# quadcopter.net
KiCad netlist of a schematic drawn in EAGLE
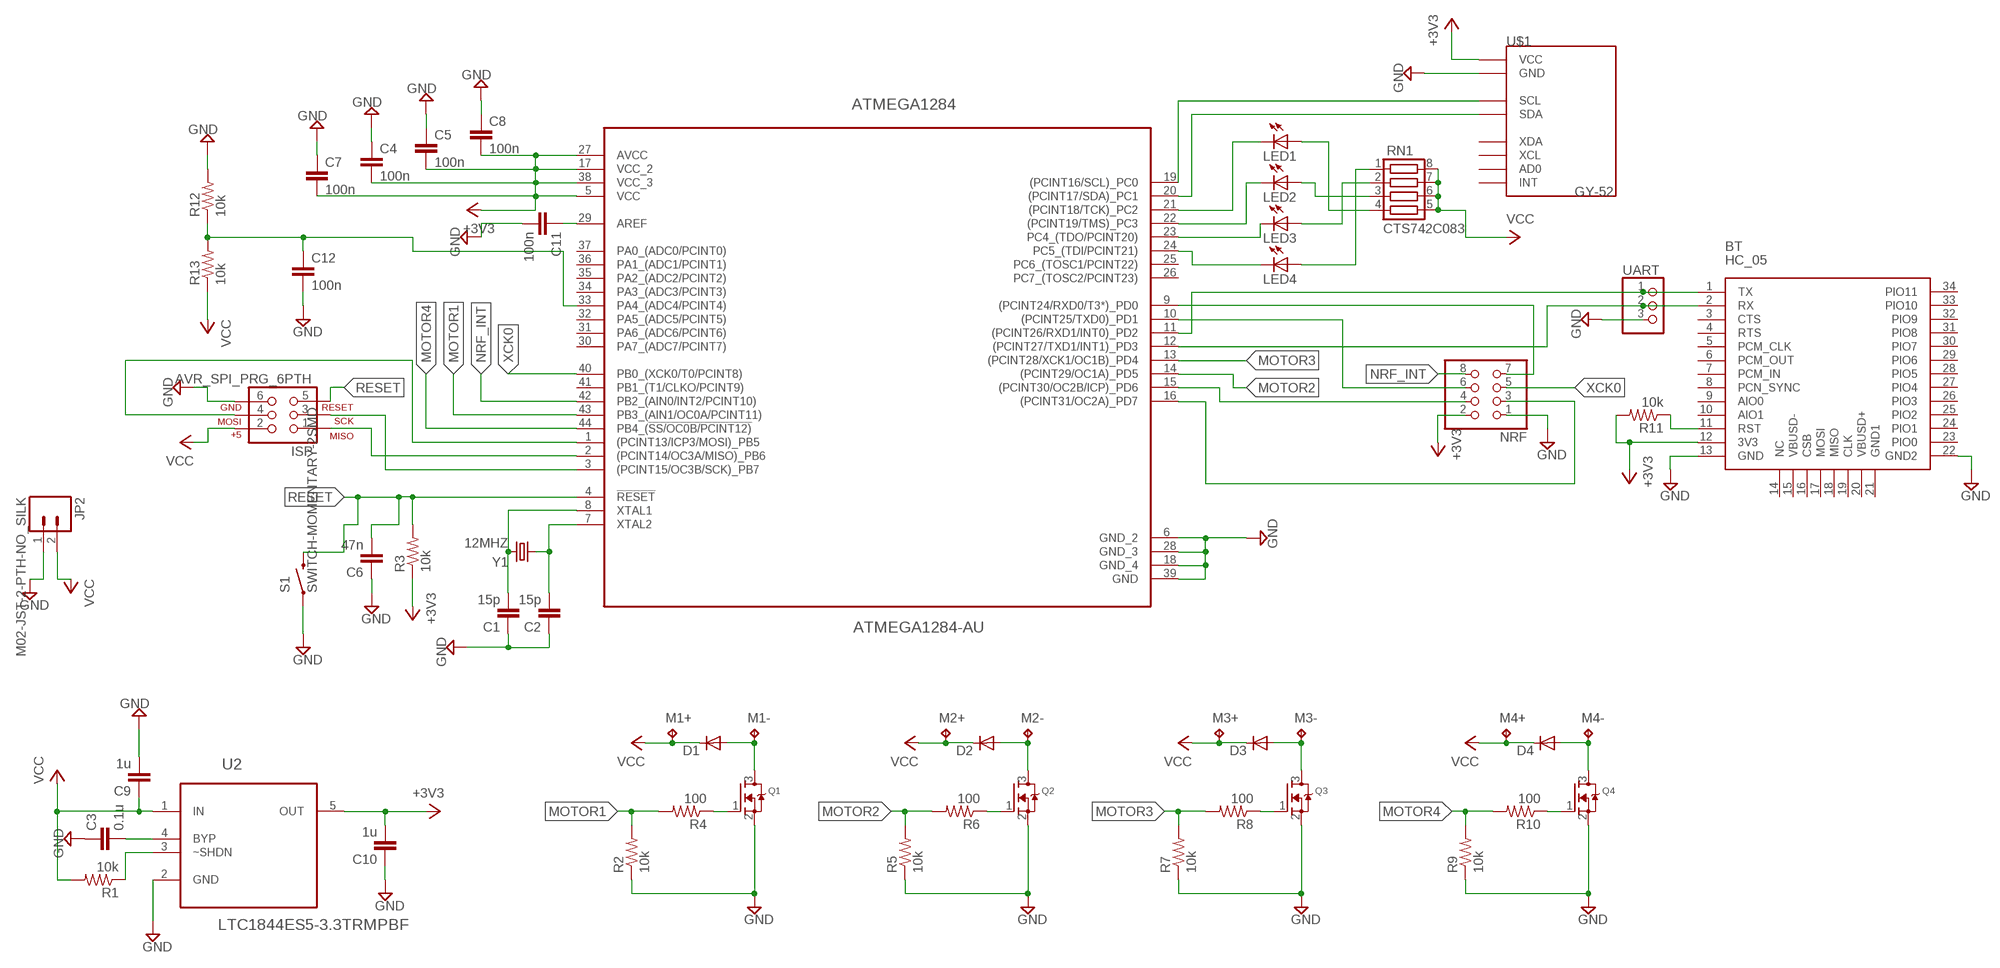
[diagram p0: schematic, sheet 1]

(export (version "E")
  (design (tool "Eeschema 10.0.6"))
  (components
    (comp (ref "ATMEGA1284")
      (value "ATMEGA1284-AU")
      (footprint "eagle-import:QFP80P1200X1200X120-44N")
      (libsource (lib "eagle-import") (part "ATMEGA1284-AU"))
    )
    (comp (ref "BT")
      (value "HC_05")
      (footprint "eagle-import:BLUETOOTH_SMD")
      (libsource (lib "eagle-import") (part "HC_05"))
    )
    (comp (ref "C1")
      (value "15p")
      (footprint "eagle-import:0603-CAP")
      (libsource (lib "eagle-import") (part "10UF-6.3V-20%(0603)"))
    )
    (comp (ref "C2")
      (value "15p")
      (footprint "eagle-import:0603-CAP")
      (libsource (lib "eagle-import") (part "10UF-6.3V-20%(0603)"))
    )
    (comp (ref "C3")
      (value "0.1u")
      (footprint "eagle-import:0603-CAP")
      (libsource (lib "eagle-import") (part "10UF-6.3V-20%(0603)"))
    )
    (comp (ref "C4")
      (value "100n")
      (footprint "eagle-import:0603-CAP")
      (libsource (lib "eagle-import") (part "10UF-6.3V-20%(0603)"))
    )
    (comp (ref "C5")
      (value "100n")
      (footprint "eagle-import:0603-CAP")
      (libsource (lib "eagle-import") (part "10UF-6.3V-20%(0603)"))
    )
    (comp (ref "C6")
      (value "47n")
      (footprint "eagle-import:0603-CAP")
      (libsource (lib "eagle-import") (part "10UF-6.3V-20%(0603)"))
    )
    (comp (ref "C7")
      (value "100n")
      (footprint "eagle-import:0603-CAP")
      (libsource (lib "eagle-import") (part "10UF-6.3V-20%(0603)"))
    )
    (comp (ref "C8")
      (value "100n")
      (footprint "eagle-import:0603-CAP")
      (libsource (lib "eagle-import") (part "10UF-6.3V-20%(0603)"))
    )
    (comp (ref "C9")
      (value "1u")
      (footprint "eagle-import:0603-CAP")
      (libsource (lib "eagle-import") (part "10UF-6.3V-20%(0603)"))
    )
    (comp (ref "C10")
      (value "1u")
      (footprint "eagle-import:0603-CAP")
      (libsource (lib "eagle-import") (part "10UF-6.3V-20%(0603)"))
    )
    (comp (ref "C11")
      (value "100n")
      (footprint "eagle-import:0603-CAP")
      (libsource (lib "eagle-import") (part "10UF-6.3V-20%(0603)"))
    )
    (comp (ref "C12")
      (value "100n")
      (footprint "eagle-import:0603-CAP")
      (libsource (lib "eagle-import") (part "10UF-6.3V-20%(0603)"))
    )
    (comp (ref "D1")
      (value "DIODE-SMB")
      (footprint "eagle-import:SMB")
      (libsource (lib "eagle-import") (part "DIODE-SMB"))
    )
    (comp (ref "D2")
      (value "DIODE-SMB")
      (footprint "eagle-import:SMB")
      (libsource (lib "eagle-import") (part "DIODE-SMB"))
    )
    (comp (ref "D3")
      (value "DIODE-SMB")
      (footprint "eagle-import:SMB")
      (libsource (lib "eagle-import") (part "DIODE-SMB"))
    )
    (comp (ref "D4")
      (value "DIODE-SMB")
      (footprint "eagle-import:SMB")
      (libsource (lib "eagle-import") (part "DIODE-SMB"))
    )
    (comp (ref "ISP")
      (value "AVR_SPI_PRG_6PTH")
      (footprint "eagle-import:2X3")
      (libsource (lib "eagle-import") (part "AVR_SPI_PRG_6PTH"))
    )
    (comp (ref "JP2")
      (value "M02-JST-2-PTH-NO_SILK")
      (footprint "eagle-import:JST-2-PTH-NS")
      (libsource (lib "eagle-import") (part "M02-JST-2-PTH-NO_SILK"))
    )
    (comp (ref "LED1")
      (value "LEDCHIP-LED0805")
      (footprint "eagle-import:CHIP-LED0805")
      (libsource (lib "eagle-import") (part "LEDCHIP-LED0805"))
    )
    (comp (ref "LED2")
      (value "LEDCHIP-LED0805")
      (footprint "eagle-import:CHIP-LED0805")
      (libsource (lib "eagle-import") (part "LEDCHIP-LED0805"))
    )
    (comp (ref "LED3")
      (value "LEDCHIP-LED0805")
      (footprint "eagle-import:CHIP-LED0805")
      (libsource (lib "eagle-import") (part "LEDCHIP-LED0805"))
    )
    (comp (ref "LED4")
      (value "LEDCHIP-LED0805")
      (footprint "eagle-import:CHIP-LED0805")
      (libsource (lib "eagle-import") (part "LEDCHIP-LED0805"))
    )
    (comp (ref "M1+")
      (value "TPTP20SQ")
      (footprint "eagle-import:TP20SQ")
      (libsource (lib "eagle-import") (part "TPTP20SQ"))
    )
    (comp (ref "M1-")
      (value "TPTP20SQ")
      (footprint "eagle-import:TP20SQ")
      (libsource (lib "eagle-import") (part "TPTP20SQ"))
    )
    (comp (ref "M2+")
      (value "TPTP20SQ")
      (footprint "eagle-import:TP20SQ")
      (libsource (lib "eagle-import") (part "TPTP20SQ"))
    )
    (comp (ref "M2-")
      (value "TPTP20SQ")
      (footprint "eagle-import:TP20SQ")
      (libsource (lib "eagle-import") (part "TPTP20SQ"))
    )
    (comp (ref "M3+")
      (value "TPTP20SQ")
      (footprint "eagle-import:TP20SQ")
      (libsource (lib "eagle-import") (part "TPTP20SQ"))
    )
    (comp (ref "M3-")
      (value "TPTP20SQ")
      (footprint "eagle-import:TP20SQ")
      (libsource (lib "eagle-import") (part "TPTP20SQ"))
    )
    (comp (ref "M4+")
      (value "TPTP20SQ")
      (footprint "eagle-import:TP20SQ")
      (libsource (lib "eagle-import") (part "TPTP20SQ"))
    )
    (comp (ref "M4-")
      (value "TPTP20SQ")
      (footprint "eagle-import:TP20SQ")
      (libsource (lib "eagle-import") (part "TPTP20SQ"))
    )
    (comp (ref "NRF")
      (value "PINHD-2X4")
      (footprint "eagle-import:2X04")
      (libsource (lib "eagle-import") (part "PINHD-2X4"))
    )
    (comp (ref "Q1")
      (value "MOSFET-NREFLOW")
      (footprint "eagle-import:SOT23")
      (libsource (lib "eagle-import") (part "MOSFET-NREFLOW"))
    )
    (comp (ref "Q2")
      (value "MOSFET-NREFLOW")
      (footprint "eagle-import:SOT23")
      (libsource (lib "eagle-import") (part "MOSFET-NREFLOW"))
    )
    (comp (ref "Q3")
      (value "MOSFET-NREFLOW")
      (footprint "eagle-import:SOT23")
      (libsource (lib "eagle-import") (part "MOSFET-NREFLOW"))
    )
    (comp (ref "Q4")
      (value "MOSFET-NREFLOW")
      (footprint "eagle-import:SOT23")
      (libsource (lib "eagle-import") (part "MOSFET-NREFLOW"))
    )
    (comp (ref "R1")
      (value "10k")
      (footprint "eagle-import:0603-RES")
      (libsource (lib "eagle-import") (part "2.0KOHM1/10W5%(0603)"))
    )
    (comp (ref "R2")
      (value "10k")
      (footprint "eagle-import:0603-RES")
      (libsource (lib "eagle-import") (part "2.0KOHM1/10W5%(0603)"))
    )
    (comp (ref "R3")
      (value "10k")
      (footprint "eagle-import:0603-RES")
      (libsource (lib "eagle-import") (part "2.0KOHM1/10W5%(0603)"))
    )
    (comp (ref "R4")
      (value "100")
      (footprint "eagle-import:0603-RES")
      (libsource (lib "eagle-import") (part "2.0KOHM1/10W5%(0603)"))
    )
    (comp (ref "R5")
      (value "10k")
      (footprint "eagle-import:0603-RES")
      (libsource (lib "eagle-import") (part "2.0KOHM1/10W5%(0603)"))
    )
    (comp (ref "R6")
      (value "100")
      (footprint "eagle-import:0603-RES")
      (libsource (lib "eagle-import") (part "2.0KOHM1/10W5%(0603)"))
    )
    (comp (ref "R7")
      (value "10k")
      (footprint "eagle-import:0603-RES")
      (libsource (lib "eagle-import") (part "2.0KOHM1/10W5%(0603)"))
    )
    (comp (ref "R8")
      (value "100")
      (footprint "eagle-import:0603-RES")
      (libsource (lib "eagle-import") (part "2.0KOHM1/10W5%(0603)"))
    )
    (comp (ref "R9")
      (value "10k")
      (footprint "eagle-import:0603-RES")
      (libsource (lib "eagle-import") (part "2.0KOHM1/10W5%(0603)"))
    )
    (comp (ref "R10")
      (value "100")
      (footprint "eagle-import:0603-RES")
      (libsource (lib "eagle-import") (part "2.0KOHM1/10W5%(0603)"))
    )
    (comp (ref "R11")
      (value "10k")
      (footprint "eagle-import:0603-RES")
      (libsource (lib "eagle-import") (part "2.0KOHM1/10W5%(0603)"))
    )
    (comp (ref "R12")
      (value "10k")
      (footprint "eagle-import:0603-RES")
      (libsource (lib "eagle-import") (part "2.0KOHM1/10W5%(0603)"))
    )
    (comp (ref "R13")
      (value "10k")
      (footprint "eagle-import:0603-RES")
      (libsource (lib "eagle-import") (part "2.0KOHM1/10W5%(0603)"))
    )
    (comp (ref "RN1")
      (value "CTS742C083")
      (footprint "eagle-import:CTS742C083")
      (libsource (lib "eagle-import") (part "CTS742C083"))
    )
    (comp (ref "S1")
      (value "SWITCH-MOMENTARY-2SMD")
      (footprint "eagle-import:TACTILE_SWITCH_SMD")
      (libsource (lib "eagle-import") (part "SWITCH-MOMENTARY-2SMD"))
    )
    (comp (ref "U$1")
      (value "GY-52")
      (footprint "eagle-import:PDIP-8")
      (libsource (lib "eagle-import") (part "GY-52"))
    )
    (comp (ref "U2")
      (value "LTC1844ES5-3.3TRMPBF")
      (footprint "eagle-import:SOT95P280X100-5N")
      (fields (field (name "MPN") "LTC1844ES5-3.3#TRMPBF"))
      (libsource (lib "eagle-import") (part "LTC1844ES5-3.3TRMPBF"))
    )
    (comp (ref "UART")
      (value "PINHD-1X3")
      (footprint "eagle-import:1X03")
      (libsource (lib "eagle-import") (part "PINHD-1X3"))
    )
    (comp (ref "Y1")
      (value "12MHZ")
      (footprint "eagle-import:TXC-SMD-CRYSTAL")
      (libsource (lib "eagle-import") (part "CRYSTAL"))
    )
  )
  (nets
    (net (code "1") (name "+3V3") (class "Default")
      (node (ref "ATMEGA1284") (pin "17") (pinfunction "VCC_2_17") (pintype "power_in"))
      (node (ref "ATMEGA1284") (pin "27") (pinfunction "AVCC_27") (pintype "power_in"))
      (node (ref "ATMEGA1284") (pin "38") (pinfunction "VCC_3_38") (pintype "power_in"))
      (node (ref "ATMEGA1284") (pin "5") (pinfunction "VCC_5") (pintype "power_in"))
      (node (ref "BT") (pin "12") (pinfunction "3V3_12") (pintype "bidirectional"))
      (node (ref "C10") (pin "2") (pinfunction "2_2") (pintype "passive"))
      (node (ref "C4") (pin "2") (pinfunction "2_2") (pintype "passive"))
      (node (ref "C5") (pin "2") (pinfunction "2_2") (pintype "passive"))
      (node (ref "C7") (pin "2") (pinfunction "2_2") (pintype "passive"))
      (node (ref "C8") (pin "2") (pinfunction "2_2") (pintype "passive"))
      (node (ref "NRF") (pin "2") (pinfunction "2_2") (pintype "passive"))
      (node (ref "R11") (pin "2") (pinfunction "2_2") (pintype "passive"))
      (node (ref "R3") (pin "1") (pinfunction "1_1") (pintype "passive"))
      (node (ref "U$1") (pin "P$2") (pinfunction "VCC_P$2") (pintype "bidirectional"))
      (node (ref "U2") (pin "5") (pinfunction "OUT_5") (pintype "output"))
    )
    (net (code "2") (name "GND") (class "Default")
      (node (ref "ATMEGA1284") (pin "18") (pinfunction "GND_4_18") (pintype "passive"))
      (node (ref "ATMEGA1284") (pin "28") (pinfunction "GND_3_28") (pintype "passive"))
      (node (ref "ATMEGA1284") (pin "39") (pinfunction "GND_39") (pintype "passive"))
      (node (ref "ATMEGA1284") (pin "6") (pinfunction "GND_2_6") (pintype "passive"))
      (node (ref "BT") (pin "13") (pinfunction "GND_13") (pintype "bidirectional"))
      (node (ref "BT") (pin "22") (pinfunction "GND2_22") (pintype "bidirectional"))
      (node (ref "C1") (pin "1") (pinfunction "1_1") (pintype "passive"))
      (node (ref "C10") (pin "1") (pinfunction "1_1") (pintype "passive"))
      (node (ref "C11") (pin "2") (pinfunction "2_2") (pintype "passive"))
      (node (ref "C12") (pin "2") (pinfunction "2_2") (pintype "passive"))
      (node (ref "C2") (pin "1") (pinfunction "1_1") (pintype "passive"))
      (node (ref "C3") (pin "1") (pinfunction "1_1") (pintype "passive"))
      (node (ref "C4") (pin "1") (pinfunction "1_1") (pintype "passive"))
      (node (ref "C5") (pin "1") (pinfunction "1_1") (pintype "passive"))
      (node (ref "C6") (pin "1") (pinfunction "1_1") (pintype "passive"))
      (node (ref "C7") (pin "1") (pinfunction "1_1") (pintype "passive"))
      (node (ref "C8") (pin "1") (pinfunction "1_1") (pintype "passive"))
      (node (ref "C9") (pin "2") (pinfunction "2_2") (pintype "passive"))
      (node (ref "ISP") (pin "6") (pinfunction "6_6") (pintype "passive"))
      (node (ref "JP2") (pin "1") (pinfunction "1_1") (pintype "passive"))
      (node (ref "NRF") (pin "1") (pinfunction "1_1") (pintype "passive"))
      (node (ref "Q1") (pin "2") (pinfunction "S_2") (pintype "bidirectional"))
      (node (ref "Q2") (pin "2") (pinfunction "S_2") (pintype "bidirectional"))
      (node (ref "Q3") (pin "2") (pinfunction "S_2") (pintype "bidirectional"))
      (node (ref "Q4") (pin "2") (pinfunction "S_2") (pintype "bidirectional"))
      (node (ref "R12") (pin "2") (pinfunction "2_2") (pintype "passive"))
      (node (ref "R2") (pin "1") (pinfunction "1_1") (pintype "passive"))
      (node (ref "R5") (pin "1") (pinfunction "1_1") (pintype "passive"))
      (node (ref "R7") (pin "1") (pinfunction "1_1") (pintype "passive"))
      (node (ref "R9") (pin "1") (pinfunction "1_1") (pintype "passive"))
      (node (ref "S1") (pin "1") (pinfunction "1_1") (pintype "passive"))
      (node (ref "U$1") (pin "P$8") (pinfunction "GND_P$8") (pintype "bidirectional"))
      (node (ref "U2") (pin "2") (pinfunction "GND_2") (pintype "passive"))
      (node (ref "UART") (pin "3") (pinfunction "3_3") (pintype "passive"))
    )
    (net (code "3") (name "MOTOR1") (class "Default")
      (node (ref "ATMEGA1284") (pin "43") (pinfunction "PB3_(AIN1/OC0A/PCINT11)_43") (pintype "bidirectional"))
      (node (ref "R2") (pin "2") (pinfunction "2_2") (pintype "passive"))
      (node (ref "R4") (pin "2") (pinfunction "2_2") (pintype "passive"))
    )
    (net (code "4") (name "MOTOR2") (class "Default")
      (node (ref "ATMEGA1284") (pin "14") (pinfunction "(PCINT29/OC1A)_PD5_14") (pintype "bidirectional"))
      (node (ref "R5") (pin "2") (pinfunction "2_2") (pintype "passive"))
      (node (ref "R6") (pin "2") (pinfunction "2_2") (pintype "passive"))
    )
    (net (code "5") (name "MOTOR3") (class "Default")
      (node (ref "ATMEGA1284") (pin "13") (pinfunction "(PCINT28/XCK1/OC1B)_PD4_13") (pintype "bidirectional"))
      (node (ref "R7") (pin "2") (pinfunction "2_2") (pintype "passive"))
      (node (ref "R8") (pin "2") (pinfunction "2_2") (pintype "passive"))
    )
    (net (code "6") (name "MOTOR4") (class "Default")
      (node (ref "ATMEGA1284") (pin "44") (pinfunction "PB4_(~{SS/OC0B/PCINT12})_44") (pintype "bidirectional"))
      (node (ref "R10") (pin "2") (pinfunction "2_2") (pintype "passive"))
      (node (ref "R9") (pin "2") (pinfunction "2_2") (pintype "passive"))
    )
    (net (code "7") (name "NRF_INT") (class "Default")
      (node (ref "ATMEGA1284") (pin "42") (pinfunction "PB2_(AIN0/INT2/PCINT10)_42") (pintype "bidirectional"))
      (node (ref "NRF") (pin "8") (pinfunction "8_8") (pintype "passive"))
    )
    (net (code "8") (name "Net-(ATMEGA1284-(PCINT13{slash}ICP3{slash}MOSI)_PB5)") (class "Default")
      (node (ref "ATMEGA1284") (pin "1") (pinfunction "(PCINT13/ICP3/MOSI)_PB5_1") (pintype "bidirectional"))
      (node (ref "ISP") (pin "4") (pinfunction "4_4") (pintype "passive"))
    )
    (net (code "9") (name "Net-(ATMEGA1284-(PCINT14{slash}OC3A{slash}MISO)_PB6)") (class "Default")
      (node (ref "ATMEGA1284") (pin "2") (pinfunction "(PCINT14/OC3A/MISO)_PB6_2") (pintype "bidirectional"))
      (node (ref "ISP") (pin "1") (pinfunction "1_1") (pintype "passive"))
    )
    (net (code "10") (name "Net-(ATMEGA1284-(PCINT15{slash}OC3B{slash}SCK)_PB7)") (class "Default")
      (node (ref "ATMEGA1284") (pin "3") (pinfunction "(PCINT15/OC3B/SCK)_PB7_3") (pintype "bidirectional"))
      (node (ref "ISP") (pin "3") (pinfunction "3_3") (pintype "passive"))
    )
    (net (code "11") (name "Net-(ATMEGA1284-(PCINT16{slash}SCL)_PC0)") (class "Default")
      (node (ref "ATMEGA1284") (pin "19") (pinfunction "(PCINT16/SCL)_PC0_19") (pintype "bidirectional"))
      (node (ref "U$1") (pin "P$6") (pinfunction "SCL_P$6") (pintype "bidirectional"))
    )
    (net (code "12") (name "Net-(ATMEGA1284-(PCINT17{slash}SDA)_PC1)") (class "Default")
      (node (ref "ATMEGA1284") (pin "20") (pinfunction "(PCINT17/SDA)_PC1_20") (pintype "bidirectional"))
      (node (ref "U$1") (pin "P$7") (pinfunction "SDA_P$7") (pintype "bidirectional"))
    )
    (net (code "13") (name "Net-(ATMEGA1284-(PCINT18{slash}TCK)_PC2)") (class "Default")
      (node (ref "ATMEGA1284") (pin "21") (pinfunction "(PCINT18/TCK)_PC2_21") (pintype "bidirectional"))
      (node (ref "LED1") (pin "C") (pinfunction "C_C") (pintype "passive"))
    )
    (net (code "14") (name "Net-(ATMEGA1284-(PCINT19{slash}TMS)_PC3)") (class "Default")
      (node (ref "ATMEGA1284") (pin "22") (pinfunction "(PCINT19/TMS)_PC3_22") (pintype "bidirectional"))
      (node (ref "LED2") (pin "C") (pinfunction "C_C") (pintype "passive"))
    )
    (net (code "15") (name "Net-(ATMEGA1284-(PCINT24{slash}RXD0{slash}T3*)_PD0)") (class "Default")
      (node (ref "ATMEGA1284") (pin "9") (pinfunction "(PCINT24/RXD0/T3*)_PD0_9") (pintype "bidirectional"))
      (node (ref "NRF") (pin "7") (pinfunction "7_7") (pintype "passive"))
    )
    (net (code "16") (name "Net-(ATMEGA1284-(PCINT25{slash}TXD0)_PD1)") (class "Default")
      (node (ref "ATMEGA1284") (pin "10") (pinfunction "(PCINT25/TXD0)_PD1_10") (pintype "bidirectional"))
      (node (ref "NRF") (pin "6") (pinfunction "6_6") (pintype "passive"))
    )
    (net (code "17") (name "Net-(ATMEGA1284-(PCINT26{slash}RXD1{slash}INT0)_PD2)") (class "Default")
      (node (ref "ATMEGA1284") (pin "11") (pinfunction "(PCINT26/RXD1/INT0)_PD2_11") (pintype "bidirectional"))
      (node (ref "BT") (pin "1") (pinfunction "TX_1") (pintype "bidirectional"))
      (node (ref "UART") (pin "1") (pinfunction "1_1") (pintype "passive"))
    )
    (net (code "18") (name "Net-(ATMEGA1284-(PCINT27{slash}TXD1{slash}INT1)_PD3)") (class "Default")
      (node (ref "ATMEGA1284") (pin "12") (pinfunction "(PCINT27/TXD1/INT1)_PD3_12") (pintype "bidirectional"))
      (node (ref "BT") (pin "2") (pinfunction "RX_2") (pintype "bidirectional"))
      (node (ref "UART") (pin "2") (pinfunction "2_2") (pintype "passive"))
    )
    (net (code "19") (name "Net-(ATMEGA1284-(PCINT30{slash}OC2B{slash}ICP)_PD6)") (class "Default")
      (node (ref "ATMEGA1284") (pin "15") (pinfunction "(PCINT30/OC2B/ICP)_PD6_15") (pintype "bidirectional"))
      (node (ref "NRF") (pin "4") (pinfunction "4_4") (pintype "passive"))
    )
    (net (code "20") (name "Net-(ATMEGA1284-(PCINT31{slash}OC2A)_PD7)") (class "Default")
      (node (ref "ATMEGA1284") (pin "16") (pinfunction "(PCINT31/OC2A)_PD7_16") (pintype "bidirectional"))
      (node (ref "NRF") (pin "3") (pinfunction "3_3") (pintype "passive"))
    )
    (net (code "21") (name "Net-(ATMEGA1284-AREF)") (class "Default")
      (node (ref "ATMEGA1284") (pin "29") (pinfunction "AREF_29") (pintype "passive"))
      (node (ref "C11") (pin "1") (pinfunction "1_1") (pintype "passive"))
    )
    (net (code "22") (name "Net-(ATMEGA1284-PA4_(ADC4{slash}PCINT4))") (class "Default")
      (node (ref "ATMEGA1284") (pin "33") (pinfunction "PA4_(ADC4/PCINT4)_33") (pintype "bidirectional"))
      (node (ref "C12") (pin "1") (pinfunction "1_1") (pintype "passive"))
      (node (ref "R12") (pin "1") (pinfunction "1_1") (pintype "passive"))
      (node (ref "R13") (pin "2") (pinfunction "2_2") (pintype "passive"))
    )
    (net (code "23") (name "Net-(ATMEGA1284-PC4_(TDO{slash}PCINT20))") (class "Default")
      (node (ref "ATMEGA1284") (pin "23") (pinfunction "PC4_(TDO/PCINT20)_23") (pintype "bidirectional"))
      (node (ref "LED3") (pin "C") (pinfunction "C_C") (pintype "passive"))
    )
    (net (code "24") (name "Net-(ATMEGA1284-PC5_(TDI{slash}PCINT21))") (class "Default")
      (node (ref "ATMEGA1284") (pin "24") (pinfunction "PC5_(TDI/PCINT21)_24") (pintype "bidirectional"))
      (node (ref "LED4") (pin "C") (pinfunction "C_C") (pintype "passive"))
    )
    (net (code "25") (name "Net-(ATMEGA1284-XTAL1)") (class "Default")
      (node (ref "ATMEGA1284") (pin "8") (pinfunction "XTAL1_8") (pintype "input"))
      (node (ref "C1") (pin "2") (pinfunction "2_2") (pintype "passive"))
      (node (ref "Y1") (pin "P$2") (pinfunction "2_P$2") (pintype "passive"))
    )
    (net (code "26") (name "Net-(ATMEGA1284-XTAL2)") (class "Default")
      (node (ref "ATMEGA1284") (pin "7") (pinfunction "XTAL2_7") (pintype "output"))
      (node (ref "C2") (pin "2") (pinfunction "2_2") (pintype "passive"))
      (node (ref "Y1") (pin "P$1") (pinfunction "1_P$1") (pintype "passive"))
    )
    (net (code "27") (name "Net-(BT-RST)") (class "Default")
      (node (ref "BT") (pin "11") (pinfunction "RST_11") (pintype "bidirectional"))
      (node (ref "R11") (pin "1") (pinfunction "1_1") (pintype "passive"))
    )
    (net (code "28") (name "Net-(LED1-PadA)") (class "Default")
      (node (ref "LED1") (pin "A") (pinfunction "A_A") (pintype "passive"))
      (node (ref "RN1") (pin "4") (pinfunction "4_4") (pintype "passive"))
    )
    (net (code "29") (name "Net-(LED2-PadA)") (class "Default")
      (node (ref "LED2") (pin "A") (pinfunction "A_A") (pintype "passive"))
      (node (ref "RN1") (pin "3") (pinfunction "3_3") (pintype "passive"))
    )
    (net (code "30") (name "Net-(LED3-PadA)") (class "Default")
      (node (ref "LED3") (pin "A") (pinfunction "A_A") (pintype "passive"))
      (node (ref "RN1") (pin "2") (pinfunction "2_2") (pintype "passive"))
    )
    (net (code "31") (name "Net-(LED4-PadA)") (class "Default")
      (node (ref "LED4") (pin "A") (pinfunction "A_A") (pintype "passive"))
      (node (ref "RN1") (pin "1") (pinfunction "1_1") (pintype "passive"))
    )
    (net (code "32") (name "Net-(Q1-D)") (class "Default")
      (node (ref "D1") (pin "A") (pinfunction "A_A") (pintype "passive"))
      (node (ref "M1-") (pin "TP") (pinfunction "TP_TP") (pintype "input"))
      (node (ref "Q1") (pin "3") (pinfunction "D_3") (pintype "bidirectional"))
    )
    (net (code "33") (name "Net-(Q1-G)") (class "Default")
      (node (ref "Q1") (pin "1") (pinfunction "G_1") (pintype "bidirectional"))
      (node (ref "R4") (pin "1") (pinfunction "1_1") (pintype "passive"))
    )
    (net (code "34") (name "Net-(Q2-D)") (class "Default")
      (node (ref "D2") (pin "A") (pinfunction "A_A") (pintype "passive"))
      (node (ref "M2-") (pin "TP") (pinfunction "TP_TP") (pintype "input"))
      (node (ref "Q2") (pin "3") (pinfunction "D_3") (pintype "bidirectional"))
    )
    (net (code "35") (name "Net-(Q2-G)") (class "Default")
      (node (ref "Q2") (pin "1") (pinfunction "G_1") (pintype "bidirectional"))
      (node (ref "R6") (pin "1") (pinfunction "1_1") (pintype "passive"))
    )
    (net (code "36") (name "Net-(Q3-D)") (class "Default")
      (node (ref "D3") (pin "A") (pinfunction "A_A") (pintype "passive"))
      (node (ref "M3-") (pin "TP") (pinfunction "TP_TP") (pintype "input"))
      (node (ref "Q3") (pin "3") (pinfunction "D_3") (pintype "bidirectional"))
    )
    (net (code "37") (name "Net-(Q3-G)") (class "Default")
      (node (ref "Q3") (pin "1") (pinfunction "G_1") (pintype "bidirectional"))
      (node (ref "R8") (pin "1") (pinfunction "1_1") (pintype "passive"))
    )
    (net (code "38") (name "Net-(Q4-D)") (class "Default")
      (node (ref "D4") (pin "A") (pinfunction "A_A") (pintype "passive"))
      (node (ref "M4-") (pin "TP") (pinfunction "TP_TP") (pintype "input"))
      (node (ref "Q4") (pin "3") (pinfunction "D_3") (pintype "bidirectional"))
    )
    (net (code "39") (name "Net-(Q4-G)") (class "Default")
      (node (ref "Q4") (pin "1") (pinfunction "G_1") (pintype "bidirectional"))
      (node (ref "R10") (pin "1") (pinfunction "1_1") (pintype "passive"))
    )
    (net (code "40") (name "Net-(U2-BYP)") (class "Default")
      (node (ref "C3") (pin "2") (pinfunction "2_2") (pintype "passive"))
      (node (ref "U2") (pin "4") (pinfunction "BYP_4") (pintype "passive"))
    )
    (net (code "41") (name "Net-(U2-~{SHDN})") (class "Default")
      (node (ref "R1") (pin "1") (pinfunction "1_1") (pintype "passive"))
      (node (ref "U2") (pin "3") (pinfunction "~{SHDN}_3") (pintype "input"))
    )
    (net (code "42") (name "RESET") (class "Default")
      (node (ref "ATMEGA1284") (pin "4") (pinfunction "~{RESET}_4") (pintype "input"))
      (node (ref "C6") (pin "2") (pinfunction "2_2") (pintype "passive"))
      (node (ref "ISP") (pin "5") (pinfunction "5_5") (pintype "passive"))
      (node (ref "R3") (pin "2") (pinfunction "2_2") (pintype "passive"))
      (node (ref "S1") (pin "3") (pinfunction "2_3") (pintype "passive"))
    )
    (net (code "43") (name "VCC") (class "Default")
      (node (ref "C9") (pin "1") (pinfunction "1_1") (pintype "passive"))
      (node (ref "D1") (pin "C") (pinfunction "C_C") (pintype "passive"))
      (node (ref "D2") (pin "C") (pinfunction "C_C") (pintype "passive"))
      (node (ref "D3") (pin "C") (pinfunction "C_C") (pintype "passive"))
      (node (ref "D4") (pin "C") (pinfunction "C_C") (pintype "passive"))
      (node (ref "ISP") (pin "2") (pinfunction "2_2") (pintype "passive"))
      (node (ref "JP2") (pin "2") (pinfunction "2_2") (pintype "passive"))
      (node (ref "M1+") (pin "TP") (pinfunction "TP_TP") (pintype "input"))
      (node (ref "M2+") (pin "TP") (pinfunction "TP_TP") (pintype "input"))
      (node (ref "M3+") (pin "TP") (pinfunction "TP_TP") (pintype "input"))
      (node (ref "M4+") (pin "TP") (pinfunction "TP_TP") (pintype "input"))
      (node (ref "R1") (pin "2") (pinfunction "2_2") (pintype "passive"))
      (node (ref "R13") (pin "1") (pinfunction "1_1") (pintype "passive"))
      (node (ref "RN1") (pin "5") (pinfunction "5_5") (pintype "passive"))
      (node (ref "RN1") (pin "6") (pinfunction "6_6") (pintype "passive"))
      (node (ref "RN1") (pin "7") (pinfunction "7_7") (pintype "passive"))
      (node (ref "RN1") (pin "8") (pinfunction "8_8") (pintype "passive"))
      (node (ref "U2") (pin "1") (pinfunction "IN_1") (pintype "power_in"))
    )
    (net (code "44") (name "XCK0") (class "Default")
      (node (ref "ATMEGA1284") (pin "40") (pinfunction "PB0_(XCK0/T0/PCINT8)_40") (pintype "bidirectional"))
      (node (ref "NRF") (pin "5") (pinfunction "5_5") (pintype "passive"))
    )
    (net (code "45") (name "unconnected-(ATMEGA1284-PA0_(ADC0{slash}PCINT0)-Pad37)") (class "Default")
      (node (ref "ATMEGA1284") (pin "37") (pinfunction "PA0_(ADC0/PCINT0)_37") (pintype "bidirectional"))
    )
    (net (code "46") (name "unconnected-(ATMEGA1284-PA1_(ADC1{slash}PCINT1)-Pad36)") (class "Default")
      (node (ref "ATMEGA1284") (pin "36") (pinfunction "PA1_(ADC1/PCINT1)_36") (pintype "bidirectional"))
    )
    (net (code "47") (name "unconnected-(ATMEGA1284-PA2_(ADC2{slash}PCINT2)-Pad35)") (class "Default")
      (node (ref "ATMEGA1284") (pin "35") (pinfunction "PA2_(ADC2/PCINT2)_35") (pintype "bidirectional"))
    )
    (net (code "48") (name "unconnected-(ATMEGA1284-PA3_(ADC3{slash}PCINT3)-Pad34)") (class "Default")
      (node (ref "ATMEGA1284") (pin "34") (pinfunction "PA3_(ADC3/PCINT3)_34") (pintype "bidirectional"))
    )
    (net (code "49") (name "unconnected-(ATMEGA1284-PA5_(ADC5{slash}PCINT5)-Pad32)") (class "Default")
      (node (ref "ATMEGA1284") (pin "32") (pinfunction "PA5_(ADC5/PCINT5)_32") (pintype "bidirectional"))
    )
    (net (code "50") (name "unconnected-(ATMEGA1284-PA6_(ADC6{slash}PCINT6)-Pad31)") (class "Default")
      (node (ref "ATMEGA1284") (pin "31") (pinfunction "PA6_(ADC6/PCINT6)_31") (pintype "bidirectional"))
    )
    (net (code "51") (name "unconnected-(ATMEGA1284-PA7_(ADC7{slash}PCINT7)-Pad30)") (class "Default")
      (node (ref "ATMEGA1284") (pin "30") (pinfunction "PA7_(ADC7/PCINT7)_30") (pintype "bidirectional"))
    )
    (net (code "52") (name "unconnected-(ATMEGA1284-PB1_(T1{slash}CLKO{slash}PCINT9)-Pad41)") (class "Default")
      (node (ref "ATMEGA1284") (pin "41") (pinfunction "PB1_(T1/CLKO/PCINT9)_41") (pintype "bidirectional"))
    )
    (net (code "53") (name "unconnected-(ATMEGA1284-PC6_(TOSC1{slash}PCINT22)-Pad25)") (class "Default")
      (node (ref "ATMEGA1284") (pin "25") (pinfunction "PC6_(TOSC1/PCINT22)_25") (pintype "bidirectional"))
    )
    (net (code "54") (name "unconnected-(ATMEGA1284-PC7_(TOSC2{slash}PCINT23)-Pad26)") (class "Default")
      (node (ref "ATMEGA1284") (pin "26") (pinfunction "PC7_(TOSC2/PCINT23)_26") (pintype "bidirectional"))
    )
    (net (code "55") (name "unconnected-(BT-AIO0-Pad9)") (class "Default")
      (node (ref "BT") (pin "9") (pinfunction "AIO0_9") (pintype "bidirectional"))
    )
    (net (code "56") (name "unconnected-(BT-AIO1-Pad10)") (class "Default")
      (node (ref "BT") (pin "10") (pinfunction "AIO1_10") (pintype "bidirectional"))
    )
    (net (code "57") (name "unconnected-(BT-CLK-Pad19)") (class "Default")
      (node (ref "BT") (pin "19") (pinfunction "CLK_19") (pintype "bidirectional"))
    )
    (net (code "58") (name "unconnected-(BT-CSB-Pad16)") (class "Default")
      (node (ref "BT") (pin "16") (pinfunction "CSB_16") (pintype "bidirectional"))
    )
    (net (code "59") (name "unconnected-(BT-CTS-Pad3)") (class "Default")
      (node (ref "BT") (pin "3") (pinfunction "CTS_3") (pintype "bidirectional"))
    )
    (net (code "60") (name "unconnected-(BT-GND1-Pad21)") (class "Default")
      (node (ref "BT") (pin "21") (pinfunction "GND1_21") (pintype "bidirectional"))
    )
    (net (code "61") (name "unconnected-(BT-MISO-Pad18)") (class "Default")
      (node (ref "BT") (pin "18") (pinfunction "MISO_18") (pintype "bidirectional"))
    )
    (net (code "62") (name "unconnected-(BT-MOSI-Pad17)") (class "Default")
      (node (ref "BT") (pin "17") (pinfunction "MOSI_17") (pintype "bidirectional"))
    )
    (net (code "63") (name "unconnected-(BT-NC-Pad14)") (class "Default")
      (node (ref "BT") (pin "14") (pinfunction "NC_14") (pintype "bidirectional"))
    )
    (net (code "64") (name "unconnected-(BT-PCM_CLK-Pad5)") (class "Default")
      (node (ref "BT") (pin "5") (pinfunction "PCM_CLK_5") (pintype "bidirectional"))
    )
    (net (code "65") (name "unconnected-(BT-PCM_IN-Pad7)") (class "Default")
      (node (ref "BT") (pin "7") (pinfunction "PCM_IN_7") (pintype "bidirectional"))
    )
    (net (code "66") (name "unconnected-(BT-PCM_OUT-Pad6)") (class "Default")
      (node (ref "BT") (pin "6") (pinfunction "PCM_OUT_6") (pintype "bidirectional"))
    )
    (net (code "67") (name "unconnected-(BT-PCN_SYNC-Pad8)") (class "Default")
      (node (ref "BT") (pin "8") (pinfunction "PCN_SYNC_8") (pintype "bidirectional"))
    )
    (net (code "68") (name "unconnected-(BT-PIO0-Pad23)") (class "Default")
      (node (ref "BT") (pin "23") (pinfunction "PIO0_23") (pintype "bidirectional"))
    )
    (net (code "69") (name "unconnected-(BT-PIO1-Pad24)") (class "Default")
      (node (ref "BT") (pin "24") (pinfunction "PIO1_24") (pintype "bidirectional"))
    )
    (net (code "70") (name "unconnected-(BT-PIO2-Pad25)") (class "Default")
      (node (ref "BT") (pin "25") (pinfunction "PIO2_25") (pintype "bidirectional"))
    )
    (net (code "71") (name "unconnected-(BT-PIO3-Pad26)") (class "Default")
      (node (ref "BT") (pin "26") (pinfunction "PIO3_26") (pintype "bidirectional"))
    )
    (net (code "72") (name "unconnected-(BT-PIO4-Pad27)") (class "Default")
      (node (ref "BT") (pin "27") (pinfunction "PIO4_27") (pintype "bidirectional"))
    )
    (net (code "73") (name "unconnected-(BT-PIO5-Pad28)") (class "Default")
      (node (ref "BT") (pin "28") (pinfunction "PIO5_28") (pintype "bidirectional"))
    )
    (net (code "74") (name "unconnected-(BT-PIO6-Pad29)") (class "Default")
      (node (ref "BT") (pin "29") (pinfunction "PIO6_29") (pintype "bidirectional"))
    )
    (net (code "75") (name "unconnected-(BT-PIO7-Pad30)") (class "Default")
      (node (ref "BT") (pin "30") (pinfunction "PIO7_30") (pintype "bidirectional"))
    )
    (net (code "76") (name "unconnected-(BT-PIO8-Pad31)") (class "Default")
      (node (ref "BT") (pin "31") (pinfunction "PIO8_31") (pintype "bidirectional"))
    )
    (net (code "77") (name "unconnected-(BT-PIO9-Pad32)") (class "Default")
      (node (ref "BT") (pin "32") (pinfunction "PIO9_32") (pintype "bidirectional"))
    )
    (net (code "78") (name "unconnected-(BT-PIO10-Pad33)") (class "Default")
      (node (ref "BT") (pin "33") (pinfunction "PIO10_33") (pintype "bidirectional"))
    )
    (net (code "79") (name "unconnected-(BT-PIO11-Pad34)") (class "Default")
      (node (ref "BT") (pin "34") (pinfunction "PIO11_34") (pintype "bidirectional"))
    )
    (net (code "80") (name "unconnected-(BT-RTS-Pad4)") (class "Default")
      (node (ref "BT") (pin "4") (pinfunction "RTS_4") (pintype "bidirectional"))
    )
    (net (code "81") (name "unconnected-(BT-VBUSD+-Pad20)") (class "Default")
      (node (ref "BT") (pin "20") (pinfunction "VBUSD+_20") (pintype "bidirectional"))
    )
    (net (code "82") (name "unconnected-(BT-VBUSD--Pad15)") (class "Default")
      (node (ref "BT") (pin "15") (pinfunction "VBUSD-_15") (pintype "bidirectional"))
    )
    (net (code "83") (name "unconnected-(U$1-AD0-PadP$4)") (class "Default")
      (node (ref "U$1") (pin "P$4") (pinfunction "AD0_P$4") (pintype "bidirectional"))
    )
    (net (code "84") (name "unconnected-(U$1-INT-PadP$5)") (class "Default")
      (node (ref "U$1") (pin "P$5") (pinfunction "INT_P$5") (pintype "bidirectional"))
    )
    (net (code "85") (name "unconnected-(U$1-XCL-PadP$3)") (class "Default")
      (node (ref "U$1") (pin "P$3") (pinfunction "XCL_P$3") (pintype "bidirectional"))
    )
    (net (code "86") (name "unconnected-(U$1-XDA-PadP$1)") (class "Default")
      (node (ref "U$1") (pin "P$1") (pinfunction "XDA_P$1") (pintype "bidirectional"))
    )
  )
)
